# MainBoardV4.net
KiCad netlist of a schematic drawn in EAGLE
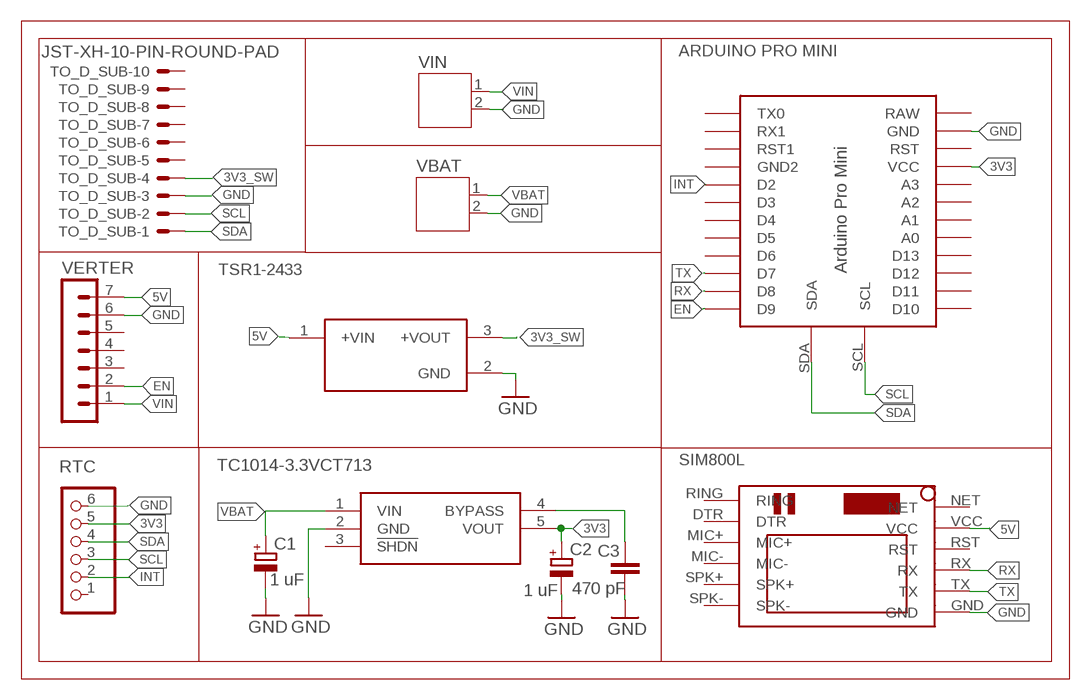
[diagram p0: schematic, sheet 1]

(export (version "E")
  (design (tool "Eeschema 10.0.6"))
  (components
    (comp (ref "C1")
      (value "1 uF")
      (footprint "eagle-import:B_3528-21R")
      (libsource (lib "eagle-import") (part "CPOL-EUB/3528-21R"))
    )
    (comp (ref "C2")
      (value "1 uF")
      (footprint "eagle-import:B_3528-21R")
      (libsource (lib "eagle-import") (part "CPOL-EUB/3528-21R"))
    )
    (comp (ref "C3")
      (value "470 pF")
      (footprint "eagle-import:C1206")
      (libsource (lib "eagle-import") (part "C-EUC1206"))
    )
    (comp (ref "RTC")
      (value "PINHD-1X6")
      (footprint "eagle-import:1X06")
      (libsource (lib "eagle-import") (part "PINHD-1X6"))
    )
    (comp (ref "TO_D_SUB")
      (value "JST-XH-10-PIN-ROUND-PAD")
      (footprint "eagle-import:JST-XH-10-PACKAGE-ROUND-PAD")
      (libsource (lib "eagle-import") (part "JST-XH-10-PIN-ROUND-PAD"))
    )
    (comp (ref "TSR1-2433")
      (value "TSR_1-2433")
      (footprint "eagle-import:CONV_TSR_1-2433")
      (fields (field (name "MF") "Traco Power") (field (name "MP") "TSR 1-2433"))
      (libsource (lib "eagle-import") (part "TSR_1-2433"))
    )
    (comp (ref "U$1")
      (value "SIM800LMODULE")
      (footprint "eagle-import:SIM800LMODULE")
      (libsource (lib "eagle-import") (part "SIM800LMODULE"))
    )
    (comp (ref "U$2")
      (value "ABK-PRO-MINI")
      (footprint "eagle-import:ABK-PRO-MINI")
      (libsource (lib "eagle-import") (part "ABK-PRO-MINI"))
    )
    (comp (ref "U1")
      (value "TC1014-3.3VCT713")
      (footprint "eagle-import:SOT95P270X130-5N")
      (fields
        (field (name "MOUSER_PART_NUMBER") "579-TC1014-3.3VCT713")
        (field (name "RS_PART_NUMBER") "2508430654")
      )
      (libsource (lib "eagle-import") (part "TC1014-3.3VCT713"))
    )
    (comp (ref "VBAT")
      (value "JST-PH2")
      (footprint "eagle-import:JST-PH2")
      (libsource (lib "eagle-import") (part "JST-PH2"))
    )
    (comp (ref "VERTER")
      (value "MA07-1")
      (footprint "eagle-import:MA07-1")
      (libsource (lib "eagle-import") (part "MA07-1"))
    )
    (comp (ref "VIN")
      (value "JST-PH2")
      (footprint "eagle-import:JST-PH2")
      (libsource (lib "eagle-import") (part "JST-PH2"))
    )
  )
  (nets
    (net (code "1") (name "3V3") (class "Default")
      (node (ref "C2") (pin "+") (pinfunction "+_+") (pintype "passive"))
      (node (ref "RTC") (pin "5") (pinfunction "5_5") (pintype "passive"))
      (node (ref "U$2") (pin "VCC") (pinfunction "VCC_VCC") (pintype "bidirectional"))
      (node (ref "U1") (pin "5") (pinfunction "VOUT_5") (pintype "output"))
    )
    (net (code "2") (name "3V3_SW") (class "Default")
      (node (ref "TO_D_SUB") (pin "4") (pinfunction "S_4") (pintype "passive"))
      (node (ref "TSR1-2433") (pin "3") (pinfunction "+VOUT_3") (pintype "output"))
    )
    (net (code "3") (name "5V") (class "Default")
      (node (ref "TSR1-2433") (pin "1") (pinfunction "+VIN_1") (pintype "input"))
      (node (ref "U$1") (pin "VCC") (pinfunction "VCC_VCC") (pintype "bidirectional"))
      (node (ref "VERTER") (pin "7") (pinfunction "7_7") (pintype "passive"))
    )
    (net (code "4") (name "EN") (class "Default")
      (node (ref "U$2") (pin "D9") (pinfunction "D9_D9") (pintype "bidirectional"))
      (node (ref "VERTER") (pin "2") (pinfunction "2_2") (pintype "passive"))
    )
    (net (code "5") (name "GND") (class "Default")
      (node (ref "C1") (pin "-") (pinfunction "-_-") (pintype "passive"))
      (node (ref "C2") (pin "-") (pinfunction "-_-") (pintype "passive"))
      (node (ref "C3") (pin "1") (pinfunction "1_1") (pintype "passive"))
      (node (ref "RTC") (pin "6") (pinfunction "6_6") (pintype "passive"))
      (node (ref "TO_D_SUB") (pin "3") (pinfunction "S_3") (pintype "passive"))
      (node (ref "TSR1-2433") (pin "2") (pinfunction "GND_2") (pintype "power_in"))
      (node (ref "U$1") (pin "GND") (pinfunction "GND_GND") (pintype "bidirectional"))
      (node (ref "U$2") (pin "GND") (pinfunction "GND_GND") (pintype "bidirectional"))
      (node (ref "U1") (pin "2") (pinfunction "GND_2") (pintype "power_in"))
      (node (ref "VBAT") (pin "2") (pinfunction "2_2") (pintype "passive"))
      (node (ref "VERTER") (pin "6") (pinfunction "6_6") (pintype "passive"))
      (node (ref "VIN") (pin "2") (pinfunction "2_2") (pintype "passive"))
    )
    (net (code "6") (name "INT") (class "Default")
      (node (ref "RTC") (pin "2") (pinfunction "2_2") (pintype "passive"))
      (node (ref "U$2") (pin "D2") (pinfunction "D2_D2") (pintype "bidirectional"))
    )
    (net (code "7") (name "Net-(U1-BYPASS)") (class "Default")
      (node (ref "C3") (pin "2") (pinfunction "2_2") (pintype "passive"))
      (node (ref "U1") (pin "4") (pinfunction "BYPASS_4") (pintype "bidirectional"))
    )
    (net (code "8") (name "RX") (class "Default")
      (node (ref "U$1") (pin "RX") (pinfunction "RX_RX") (pintype "bidirectional"))
      (node (ref "U$2") (pin "D8") (pinfunction "D8_D8") (pintype "bidirectional"))
    )
    (net (code "9") (name "SCL") (class "Default")
      (node (ref "RTC") (pin "3") (pinfunction "3_3") (pintype "passive"))
      (node (ref "TO_D_SUB") (pin "2") (pinfunction "S_2") (pintype "passive"))
      (node (ref "U$2") (pin "SCL") (pinfunction "SCL_SCL") (pintype "bidirectional"))
    )
    (net (code "10") (name "SDA") (class "Default")
      (node (ref "RTC") (pin "4") (pinfunction "4_4") (pintype "passive"))
      (node (ref "TO_D_SUB") (pin "1") (pinfunction "S_1") (pintype "passive"))
      (node (ref "U$2") (pin "SDA") (pinfunction "SDA_SDA") (pintype "bidirectional"))
    )
    (net (code "11") (name "TX") (class "Default")
      (node (ref "U$1") (pin "TX") (pinfunction "TX_TX") (pintype "bidirectional"))
      (node (ref "U$2") (pin "D7") (pinfunction "D7_D7") (pintype "bidirectional"))
    )
    (net (code "12") (name "VBAT") (class "Default")
      (node (ref "C1") (pin "+") (pinfunction "+_+") (pintype "passive"))
      (node (ref "U1") (pin "1") (pinfunction "VIN_1") (pintype "power_in"))
      (node (ref "VBAT") (pin "1") (pinfunction "1_1") (pintype "passive"))
    )
    (net (code "13") (name "VIN") (class "Default")
      (node (ref "VERTER") (pin "1") (pinfunction "1_1") (pintype "passive"))
      (node (ref "VIN") (pin "1") (pinfunction "1_1") (pintype "passive"))
    )
    (net (code "14") (name "unconnected-(RTC-Pad1)") (class "Default")
      (node (ref "RTC") (pin "1") (pinfunction "1_1") (pintype "passive"))
    )
    (net (code "15") (name "unconnected-(TO_D_SUBB-S-Pad10)") (class "Default")
      (node (ref "TO_D_SUB") (pin "10") (pinfunction "S_10") (pintype "passive"))
    )
    (net (code "16") (name "unconnected-(TO_D_SUBF-S-Pad5)") (class "Default")
      (node (ref "TO_D_SUB") (pin "5") (pinfunction "S_5") (pintype "passive"))
    )
    (net (code "17") (name "unconnected-(TO_D_SUBG-S-Pad6)") (class "Default")
      (node (ref "TO_D_SUB") (pin "6") (pinfunction "S_6") (pintype "passive"))
    )
    (net (code "18") (name "unconnected-(TO_D_SUBH-S-Pad7)") (class "Default")
      (node (ref "TO_D_SUB") (pin "7") (pinfunction "S_7") (pintype "passive"))
    )
    (net (code "19") (name "unconnected-(TO_D_SUBI-S-Pad8)") (class "Default")
      (node (ref "TO_D_SUB") (pin "8") (pinfunction "S_8") (pintype "passive"))
    )
    (net (code "20") (name "unconnected-(TO_D_SUBJ-S-Pad9)") (class "Default")
      (node (ref "TO_D_SUB") (pin "9") (pinfunction "S_9") (pintype "passive"))
    )
    (net (code "21") (name "unconnected-(U$1-PadDTR)") (class "Default")
      (node (ref "U$1") (pin "DTR") (pinfunction "DTR_DTR") (pintype "bidirectional"))
    )
    (net (code "22") (name "unconnected-(U$1-PadMIC+)") (class "Default")
      (node (ref "U$1") (pin "MIC+") (pinfunction "MIC+_MIC+") (pintype "bidirectional"))
    )
    (net (code "23") (name "unconnected-(U$1-PadMIC-)") (class "Default")
      (node (ref "U$1") (pin "MIC-") (pinfunction "MIC-_MIC-") (pintype "bidirectional"))
    )
    (net (code "24") (name "unconnected-(U$1-PadNET)") (class "Default")
      (node (ref "U$1") (pin "NET") (pinfunction "NET_NET") (pintype "bidirectional"))
    )
    (net (code "25") (name "unconnected-(U$1-PadRING)") (class "Default")
      (node (ref "U$1") (pin "RING") (pinfunction "RING_RING") (pintype "bidirectional"))
    )
    (net (code "26") (name "unconnected-(U$1-PadRST)") (class "Default")
      (node (ref "U$1") (pin "RST") (pinfunction "RST_RST") (pintype "bidirectional"))
    )
    (net (code "27") (name "unconnected-(U$1-PadSPK+)") (class "Default")
      (node (ref "U$1") (pin "SPK+") (pinfunction "SPK+_SPK+") (pintype "bidirectional"))
    )
    (net (code "28") (name "unconnected-(U$1-PadSPK-)") (class "Default")
      (node (ref "U$1") (pin "SPK-") (pinfunction "SPK-_SPK-") (pintype "bidirectional"))
    )
    (net (code "29") (name "unconnected-(U$2-GND2-PadGND1)") (class "Default")
      (node (ref "U$2") (pin "GND1") (pinfunction "GND2_GND1") (pintype "bidirectional"))
    )
    (net (code "30") (name "unconnected-(U$2-PadA0)") (class "Default")
      (node (ref "U$2") (pin "A0") (pinfunction "A0_A0") (pintype "bidirectional"))
    )
    (net (code "31") (name "unconnected-(U$2-PadA1)") (class "Default")
      (node (ref "U$2") (pin "A1") (pinfunction "A1_A1") (pintype "bidirectional"))
    )
    (net (code "32") (name "unconnected-(U$2-PadA2)") (class "Default")
      (node (ref "U$2") (pin "A2") (pinfunction "A2_A2") (pintype "bidirectional"))
    )
    (net (code "33") (name "unconnected-(U$2-PadA3)") (class "Default")
      (node (ref "U$2") (pin "A3") (pinfunction "A3_A3") (pintype "bidirectional"))
    )
    (net (code "34") (name "unconnected-(U$2-PadD3)") (class "Default")
      (node (ref "U$2") (pin "D3") (pinfunction "D3_D3") (pintype "bidirectional"))
    )
    (net (code "35") (name "unconnected-(U$2-PadD4)") (class "Default")
      (node (ref "U$2") (pin "D4") (pinfunction "D4_D4") (pintype "bidirectional"))
    )
    (net (code "36") (name "unconnected-(U$2-PadD5)") (class "Default")
      (node (ref "U$2") (pin "D5") (pinfunction "D5_D5") (pintype "bidirectional"))
    )
    (net (code "37") (name "unconnected-(U$2-PadD6)") (class "Default")
      (node (ref "U$2") (pin "D6") (pinfunction "D6_D6") (pintype "bidirectional"))
    )
    (net (code "38") (name "unconnected-(U$2-PadD10)") (class "Default")
      (node (ref "U$2") (pin "D10") (pinfunction "D10_D10") (pintype "bidirectional"))
    )
    (net (code "39") (name "unconnected-(U$2-PadD11)") (class "Default")
      (node (ref "U$2") (pin "D11") (pinfunction "D11_D11") (pintype "bidirectional"))
    )
    (net (code "40") (name "unconnected-(U$2-PadD12)") (class "Default")
      (node (ref "U$2") (pin "D12") (pinfunction "D12_D12") (pintype "bidirectional"))
    )
    (net (code "41") (name "unconnected-(U$2-PadD13)") (class "Default")
      (node (ref "U$2") (pin "D13") (pinfunction "D13_D13") (pintype "bidirectional"))
    )
    (net (code "42") (name "unconnected-(U$2-PadRAW)") (class "Default")
      (node (ref "U$2") (pin "RAW") (pinfunction "RAW_RAW") (pintype "bidirectional"))
    )
    (net (code "43") (name "unconnected-(U$2-PadRST)") (class "Default")
      (node (ref "U$2") (pin "RST") (pinfunction "RST_RST") (pintype "bidirectional"))
    )
    (net (code "44") (name "unconnected-(U$2-PadRST1)") (class "Default")
      (node (ref "U$2") (pin "RST1") (pinfunction "RST1_RST1") (pintype "bidirectional"))
    )
    (net (code "45") (name "unconnected-(U$2-PadRX1)") (class "Default")
      (node (ref "U$2") (pin "RX1") (pinfunction "RX1_RX1") (pintype "bidirectional"))
    )
    (net (code "46") (name "unconnected-(U$2-PadTX0)") (class "Default")
      (node (ref "U$2") (pin "TX0") (pinfunction "TX0_TX0") (pintype "bidirectional"))
    )
    (net (code "47") (name "unconnected-(U1-~{SHDN}-Pad3)") (class "Default")
      (node (ref "U1") (pin "3") (pinfunction "~{SHDN}_3") (pintype "input"))
    )
    (net (code "48") (name "unconnected-(VERTER-Pad3)") (class "Default")
      (node (ref "VERTER") (pin "3") (pinfunction "3_3") (pintype "passive"))
    )
    (net (code "49") (name "unconnected-(VERTER-Pad4)") (class "Default")
      (node (ref "VERTER") (pin "4") (pinfunction "4_4") (pintype "passive"))
    )
    (net (code "50") (name "unconnected-(VERTER-Pad5)") (class "Default")
      (node (ref "VERTER") (pin "5") (pinfunction "5_5") (pintype "passive"))
    )
  )
)
